# nRF52-AvmBeacon23cmMonopole.net
KiCad netlist of a schematic drawn in EAGLE
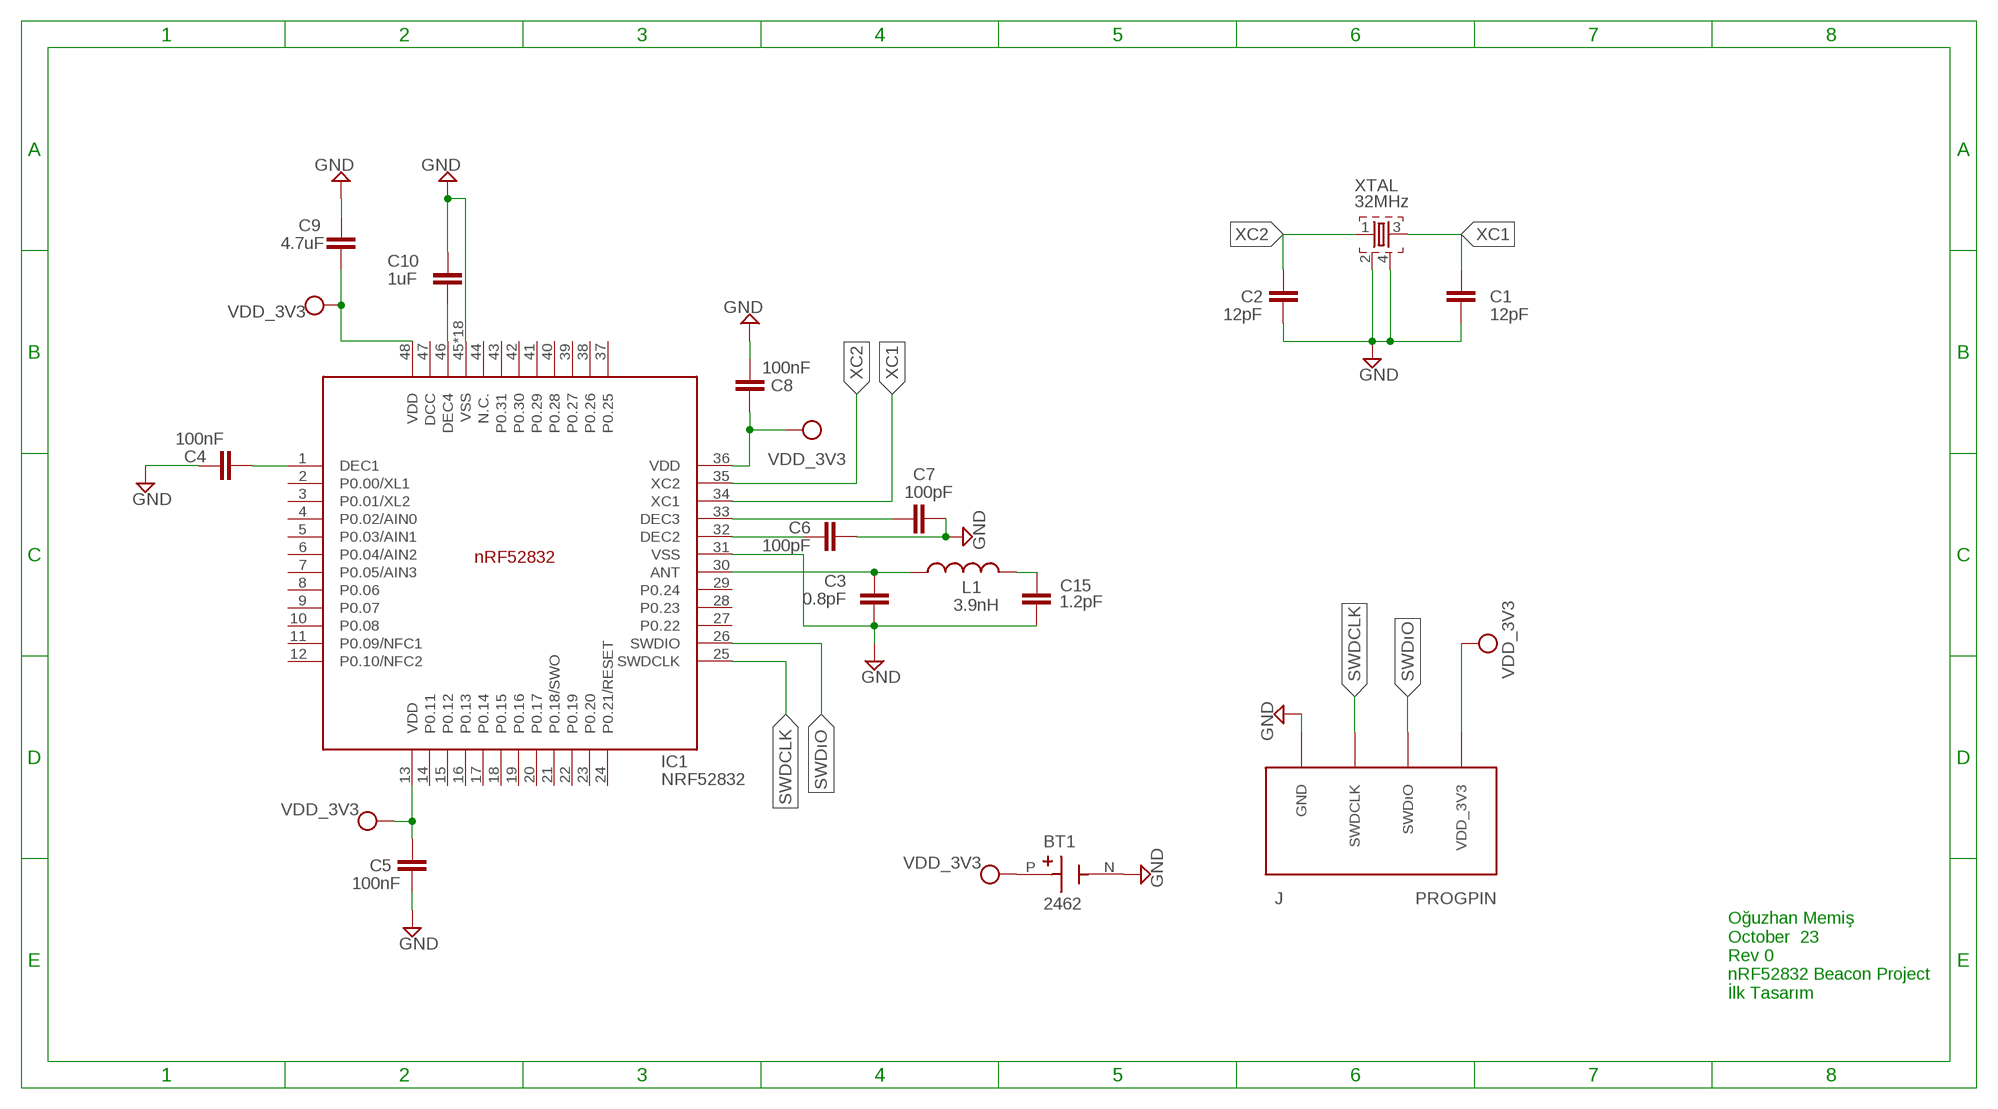
[diagram p0: schematic, sheet 1]

(export (version "E")
  (design (tool "Eeschema 10.0.6"))
  (components
    (comp (ref "BT1")
      (value "2462")
      (footprint "eagle-import:BAT_2462")
      (fields (field (name "MF") "Keystone"))
      (libsource (lib "eagle-import") (part "2462"))
    )
    (comp (ref "C1")
      (value "12pF")
      (footprint "eagle-import:RESC0402_N")
      (libsource (lib "eagle-import") (part "CAPACITOR_0402_N"))
    )
    (comp (ref "C2")
      (value "12pF")
      (footprint "eagle-import:RESC0402_N")
      (libsource (lib "eagle-import") (part "CAPACITOR_0402_N"))
    )
    (comp (ref "C3")
      (value "0.8pF")
      (footprint "eagle-import:RESC0402_N")
      (libsource (lib "eagle-import") (part "CAPACITOR_0402_N"))
    )
    (comp (ref "C4")
      (value "100nF")
      (footprint "eagle-import:RESC0402_N")
      (libsource (lib "eagle-import") (part "CAPACITOR_0402_N"))
    )
    (comp (ref "C5")
      (value "100nF")
      (footprint "eagle-import:RESC0402_N")
      (libsource (lib "eagle-import") (part "CAPACITOR_0402_N"))
    )
    (comp (ref "C6")
      (value "100pF")
      (footprint "eagle-import:RESC0402_N")
      (libsource (lib "eagle-import") (part "CAPACITOR_0402_N"))
    )
    (comp (ref "C7")
      (value "100pF")
      (footprint "eagle-import:RESC0402_N")
      (libsource (lib "eagle-import") (part "CAPACITOR_0402_N"))
    )
    (comp (ref "C8")
      (value "100nF")
      (footprint "eagle-import:RESC0402_N")
      (libsource (lib "eagle-import") (part "CAPACITOR_0402_N"))
    )
    (comp (ref "C9")
      (value "4.7uF")
      (footprint "eagle-import:RESC0603_N")
      (libsource (lib "eagle-import") (part "CAPACITOR_0603_N"))
    )
    (comp (ref "C10")
      (value "1uF")
      (footprint "eagle-import:RESC0603_N")
      (libsource (lib "eagle-import") (part "CAPACITOR_0603_N"))
    )
    (comp (ref "C15")
      (value "1.2pF")
      (footprint "eagle-import:RESC0402_N")
      (libsource (lib "eagle-import") (part "Nordic_nRF_169009_CAPACITOR_0402_N"))
    )
    (comp (ref "IC1")
      (value "NRF52832")
      (footprint "eagle-import:QFN40P600X600X90-48_N")
      (libsource (lib "eagle-import") (part "NRF52832"))
    )
    (comp (ref "L1")
      (value "3.9nH")
      (footprint "eagle-import:RESC0402_N")
      (libsource (lib "eagle-import") (part "INDUCTOR_0402_N"))
    )
    (comp (ref "U$1")
      (value "PROGPIN4*2.54")
      (footprint "eagle-import:PROGPIN")
      (libsource (lib "eagle-import") (part "PROGPIN42.54"))
    )
    (comp (ref "XTAL")
      (value "32MHz")
      (footprint "eagle-import:BT-XTAL_2016_N")
      (libsource (lib "eagle-import") (part "XTAL_32MHZ"))
    )
  )
  (nets
    (net (code "1") (name "GND") (class "Default")
      (node (ref "BT1") (pin "N") (pinfunction "NEG_N") (pintype "passive"))
      (node (ref "C1") (pin "2") (pinfunction "2_2") (pintype "passive"))
      (node (ref "C10") (pin "1") (pinfunction "1_1") (pintype "passive"))
      (node (ref "C15") (pin "2") (pinfunction "2_2") (pintype "passive"))
      (node (ref "C2") (pin "2") (pinfunction "2_2") (pintype "passive"))
      (node (ref "C3") (pin "1") (pinfunction "1_1") (pintype "passive"))
      (node (ref "C4") (pin "1") (pinfunction "1_1") (pintype "passive"))
      (node (ref "C5") (pin "2") (pinfunction "2_2") (pintype "passive"))
      (node (ref "C6") (pin "2") (pinfunction "2_2") (pintype "passive"))
      (node (ref "C7") (pin "2") (pinfunction "2_2") (pintype "passive"))
      (node (ref "C8") (pin "2") (pinfunction "2_2") (pintype "passive"))
      (node (ref "C9") (pin "1") (pinfunction "1_1") (pintype "passive"))
      (node (ref "IC1") (pin "31") (pinfunction "VSS_31") (pintype "bidirectional"))
      (node (ref "IC1") (pin "45") (pinfunction "VSS_45") (pintype "power_in"))
      (node (ref "IC1") (pin "PAD") (pinfunction "VSS_PAD") (pintype "power_in"))
      (node (ref "IC1") (pin "PAD@VIA01") (pinfunction "VSS_PAD@VIA01") (pintype "power_in"))
      (node (ref "IC1") (pin "PAD@VIA02") (pinfunction "VSS_PAD@VIA02") (pintype "power_in"))
      (node (ref "IC1") (pin "PAD@VIA03") (pinfunction "VSS_PAD@VIA03") (pintype "power_in"))
      (node (ref "IC1") (pin "PAD@VIA04") (pinfunction "VSS_PAD@VIA04") (pintype "power_in"))
      (node (ref "IC1") (pin "PAD@VIA05") (pinfunction "VSS_PAD@VIA05") (pintype "power_in"))
      (node (ref "IC1") (pin "PAD@VIA06") (pinfunction "VSS_PAD@VIA06") (pintype "power_in"))
      (node (ref "IC1") (pin "PAD@VIA07") (pinfunction "VSS_PAD@VIA07") (pintype "power_in"))
      (node (ref "IC1") (pin "PAD@VIA08") (pinfunction "VSS_PAD@VIA08") (pintype "power_in"))
      (node (ref "IC1") (pin "PAD@VIA09") (pinfunction "VSS_PAD@VIA09") (pintype "power_in"))
      (node (ref "IC1") (pin "PAD@VIA10") (pinfunction "VSS_PAD@VIA10") (pintype "power_in"))
      (node (ref "IC1") (pin "PAD@VIA11") (pinfunction "VSS_PAD@VIA11") (pintype "power_in"))
      (node (ref "IC1") (pin "PAD@VIA12") (pinfunction "VSS_PAD@VIA12") (pintype "power_in"))
      (node (ref "IC1") (pin "PAD@VIA13") (pinfunction "VSS_PAD@VIA13") (pintype "power_in"))
      (node (ref "IC1") (pin "PAD@VIA14") (pinfunction "VSS_PAD@VIA14") (pintype "power_in"))
      (node (ref "IC1") (pin "PAD@VIA15") (pinfunction "VSS_PAD@VIA15") (pintype "power_in"))
      (node (ref "IC1") (pin "PAD@VIA16") (pinfunction "VSS_PAD@VIA16") (pintype "power_in"))
      (node (ref "U$1") (pin "GND") (pinfunction "GND_GND") (pintype "bidirectional"))
      (node (ref "XTAL") (pin "2") (pinfunction "2_2") (pintype "passive"))
      (node (ref "XTAL") (pin "4") (pinfunction "4_4") (pintype "passive"))
    )
    (net (code "2") (name "Net-(C15-Pad1)") (class "Default")
      (node (ref "C15") (pin "1") (pinfunction "1_1") (pintype "passive"))
      (node (ref "L1") (pin "2") (pinfunction "2_2") (pintype "passive"))
    )
    (net (code "3") (name "Net-(IC1-ANT)") (class "Default")
      (node (ref "C3") (pin "2") (pinfunction "2_2") (pintype "passive"))
      (node (ref "IC1") (pin "30") (pinfunction "ANT_30") (pintype "bidirectional"))
      (node (ref "L1") (pin "1") (pinfunction "1_1") (pintype "passive"))
    )
    (net (code "4") (name "Net-(IC1-DEC1)") (class "Default")
      (node (ref "C4") (pin "2") (pinfunction "2_2") (pintype "passive"))
      (node (ref "IC1") (pin "1") (pinfunction "DEC1_1") (pintype "power_in"))
    )
    (net (code "5") (name "Net-(IC1-DEC2)") (class "Default")
      (node (ref "C6") (pin "1") (pinfunction "1_1") (pintype "passive"))
      (node (ref "IC1") (pin "32") (pinfunction "DEC2_32") (pintype "bidirectional"))
    )
    (net (code "6") (name "Net-(IC1-DEC3)") (class "Default")
      (node (ref "C7") (pin "1") (pinfunction "1_1") (pintype "passive"))
      (node (ref "IC1") (pin "33") (pinfunction "DEC3_33") (pintype "bidirectional"))
    )
    (net (code "7") (name "Net-(IC1-DEC4)") (class "Default")
      (node (ref "C10") (pin "2") (pinfunction "2_2") (pintype "passive"))
      (node (ref "IC1") (pin "46") (pinfunction "DEC4_46") (pintype "power_in"))
    )
    (net (code "8") (name "SWDCLK") (class "Default")
      (node (ref "IC1") (pin "25") (pinfunction "SWDCLK_25") (pintype "input"))
      (node (ref "U$1") (pin "SWDCLK") (pinfunction "SWDCLK_SWDCLK") (pintype "bidirectional"))
    )
    (net (code "9") (name "SWDıO") (class "Default")
      (node (ref "IC1") (pin "26") (pinfunction "SWDIO_26") (pintype "bidirectional"))
      (node (ref "U$1") (pin "SWDIO") (pinfunction "SWDıO_SWDIO") (pintype "bidirectional"))
    )
    (net (code "10") (name "VDD") (class "Default")
      (node (ref "BT1") (pin "P") (pinfunction "POS_P") (pintype "passive"))
      (node (ref "C5") (pin "1") (pinfunction "1_1") (pintype "passive"))
      (node (ref "C8") (pin "1") (pinfunction "1_1") (pintype "passive"))
      (node (ref "C9") (pin "2") (pinfunction "2_2") (pintype "passive"))
      (node (ref "IC1") (pin "13") (pinfunction "VDD_13") (pintype "power_in"))
      (node (ref "IC1") (pin "36") (pinfunction "VDD_36") (pintype "power_in"))
      (node (ref "IC1") (pin "48") (pinfunction "VDD_48") (pintype "power_in"))
      (node (ref "U$1") (pin "VDD_3V3") (pinfunction "VDD_3V3_VDD_3V3") (pintype "bidirectional"))
    )
    (net (code "11") (name "XC1") (class "Default")
      (node (ref "C1") (pin "1") (pinfunction "1_1") (pintype "passive"))
      (node (ref "IC1") (pin "34") (pinfunction "XC1_34") (pintype "input"))
      (node (ref "XTAL") (pin "3") (pinfunction "3_3") (pintype "passive"))
    )
    (net (code "12") (name "XC2") (class "Default")
      (node (ref "C2") (pin "1") (pinfunction "1_1") (pintype "passive"))
      (node (ref "IC1") (pin "35") (pinfunction "XC2_35") (pintype "output"))
      (node (ref "XTAL") (pin "1") (pinfunction "1_1") (pintype "passive"))
    )
    (net (code "13") (name "unconnected-(IC1-DCC-Pad47)") (class "Default")
      (node (ref "IC1") (pin "47") (pinfunction "DCC_47") (pintype "output"))
    )
    (net (code "14") (name "unconnected-(IC1-N.C.-Pad44)") (class "Default")
      (node (ref "IC1") (pin "44") (pinfunction "N.C._44") (pintype "no_connect"))
    )
    (net (code "15") (name "unconnected-(IC1-P0.00{slash}XL1-Pad2)") (class "Default")
      (node (ref "IC1") (pin "2") (pinfunction "P0.00/XL1_2") (pintype "bidirectional"))
    )
    (net (code "16") (name "unconnected-(IC1-P0.01{slash}XL2-Pad3)") (class "Default")
      (node (ref "IC1") (pin "3") (pinfunction "P0.01/XL2_3") (pintype "bidirectional"))
    )
    (net (code "17") (name "unconnected-(IC1-P0.02{slash}AIN0-Pad4)") (class "Default")
      (node (ref "IC1") (pin "4") (pinfunction "P0.02/AIN0_4") (pintype "bidirectional"))
    )
    (net (code "18") (name "unconnected-(IC1-P0.03{slash}AIN1-Pad5)") (class "Default")
      (node (ref "IC1") (pin "5") (pinfunction "P0.03/AIN1_5") (pintype "bidirectional"))
    )
    (net (code "19") (name "unconnected-(IC1-P0.04{slash}AIN2-Pad6)") (class "Default")
      (node (ref "IC1") (pin "6") (pinfunction "P0.04/AIN2_6") (pintype "bidirectional"))
    )
    (net (code "20") (name "unconnected-(IC1-P0.05{slash}AIN3-Pad7)") (class "Default")
      (node (ref "IC1") (pin "7") (pinfunction "P0.05/AIN3_7") (pintype "bidirectional"))
    )
    (net (code "21") (name "unconnected-(IC1-P0.06-Pad8)") (class "Default")
      (node (ref "IC1") (pin "8") (pinfunction "P0.06_8") (pintype "bidirectional"))
    )
    (net (code "22") (name "unconnected-(IC1-P0.07-Pad9)") (class "Default")
      (node (ref "IC1") (pin "9") (pinfunction "P0.07_9") (pintype "bidirectional"))
    )
    (net (code "23") (name "unconnected-(IC1-P0.08-Pad10)") (class "Default")
      (node (ref "IC1") (pin "10") (pinfunction "P0.08_10") (pintype "bidirectional"))
    )
    (net (code "24") (name "unconnected-(IC1-P0.09{slash}NFC1-Pad11)") (class "Default")
      (node (ref "IC1") (pin "11") (pinfunction "P0.09/NFC1_11") (pintype "bidirectional"))
    )
    (net (code "25") (name "unconnected-(IC1-P0.10{slash}NFC2-Pad12)") (class "Default")
      (node (ref "IC1") (pin "12") (pinfunction "P0.10/NFC2_12") (pintype "bidirectional"))
    )
    (net (code "26") (name "unconnected-(IC1-P0.11-Pad14)") (class "Default")
      (node (ref "IC1") (pin "14") (pinfunction "P0.11_14") (pintype "bidirectional"))
    )
    (net (code "27") (name "unconnected-(IC1-P0.12-Pad15)") (class "Default")
      (node (ref "IC1") (pin "15") (pinfunction "P0.12_15") (pintype "bidirectional"))
    )
    (net (code "28") (name "unconnected-(IC1-P0.13-Pad16)") (class "Default")
      (node (ref "IC1") (pin "16") (pinfunction "P0.13_16") (pintype "bidirectional"))
    )
    (net (code "29") (name "unconnected-(IC1-P0.14-Pad17)") (class "Default")
      (node (ref "IC1") (pin "17") (pinfunction "P0.14_17") (pintype "bidirectional"))
    )
    (net (code "30") (name "unconnected-(IC1-P0.15-Pad18)") (class "Default")
      (node (ref "IC1") (pin "18") (pinfunction "P0.15_18") (pintype "bidirectional"))
    )
    (net (code "31") (name "unconnected-(IC1-P0.16-Pad19)") (class "Default")
      (node (ref "IC1") (pin "19") (pinfunction "P0.16_19") (pintype "bidirectional"))
    )
    (net (code "32") (name "unconnected-(IC1-P0.17-Pad20)") (class "Default")
      (node (ref "IC1") (pin "20") (pinfunction "P0.17_20") (pintype "bidirectional"))
    )
    (net (code "33") (name "unconnected-(IC1-P0.18{slash}SWO-Pad21)") (class "Default")
      (node (ref "IC1") (pin "21") (pinfunction "P0.18/SWO_21") (pintype "bidirectional"))
    )
    (net (code "34") (name "unconnected-(IC1-P0.19-Pad22)") (class "Default")
      (node (ref "IC1") (pin "22") (pinfunction "P0.19_22") (pintype "bidirectional"))
    )
    (net (code "35") (name "unconnected-(IC1-P0.20-Pad23)") (class "Default")
      (node (ref "IC1") (pin "23") (pinfunction "P0.20_23") (pintype "bidirectional"))
    )
    (net (code "36") (name "unconnected-(IC1-P0.21{slash}RESET-Pad24)") (class "Default")
      (node (ref "IC1") (pin "24") (pinfunction "P0.21/RESET_24") (pintype "bidirectional"))
    )
    (net (code "37") (name "unconnected-(IC1-P0.22-Pad27)") (class "Default")
      (node (ref "IC1") (pin "27") (pinfunction "P0.22_27") (pintype "bidirectional"))
    )
    (net (code "38") (name "unconnected-(IC1-P0.23-Pad28)") (class "Default")
      (node (ref "IC1") (pin "28") (pinfunction "P0.23_28") (pintype "bidirectional"))
    )
    (net (code "39") (name "unconnected-(IC1-P0.24-Pad29)") (class "Default")
      (node (ref "IC1") (pin "29") (pinfunction "P0.24_29") (pintype "bidirectional"))
    )
    (net (code "40") (name "unconnected-(IC1-P0.25-Pad37)") (class "Default")
      (node (ref "IC1") (pin "37") (pinfunction "P0.25_37") (pintype "bidirectional"))
    )
    (net (code "41") (name "unconnected-(IC1-P0.26-Pad38)") (class "Default")
      (node (ref "IC1") (pin "38") (pinfunction "P0.26_38") (pintype "bidirectional"))
    )
    (net (code "42") (name "unconnected-(IC1-P0.27-Pad39)") (class "Default")
      (node (ref "IC1") (pin "39") (pinfunction "P0.27_39") (pintype "bidirectional"))
    )
    (net (code "43") (name "unconnected-(IC1-P0.28-Pad40)") (class "Default")
      (node (ref "IC1") (pin "40") (pinfunction "P0.28_40") (pintype "bidirectional"))
    )
    (net (code "44") (name "unconnected-(IC1-P0.29-Pad41)") (class "Default")
      (node (ref "IC1") (pin "41") (pinfunction "P0.29_41") (pintype "bidirectional"))
    )
    (net (code "45") (name "unconnected-(IC1-P0.30-Pad42)") (class "Default")
      (node (ref "IC1") (pin "42") (pinfunction "P0.30_42") (pintype "bidirectional"))
    )
    (net (code "46") (name "unconnected-(IC1-P0.31-Pad43)") (class "Default")
      (node (ref "IC1") (pin "43") (pinfunction "P0.31_43") (pintype "bidirectional"))
    )
  )
)
